# Motor_Driver_Board_V1_0.net
KiCad netlist of a schematic drawn in Altium Designer
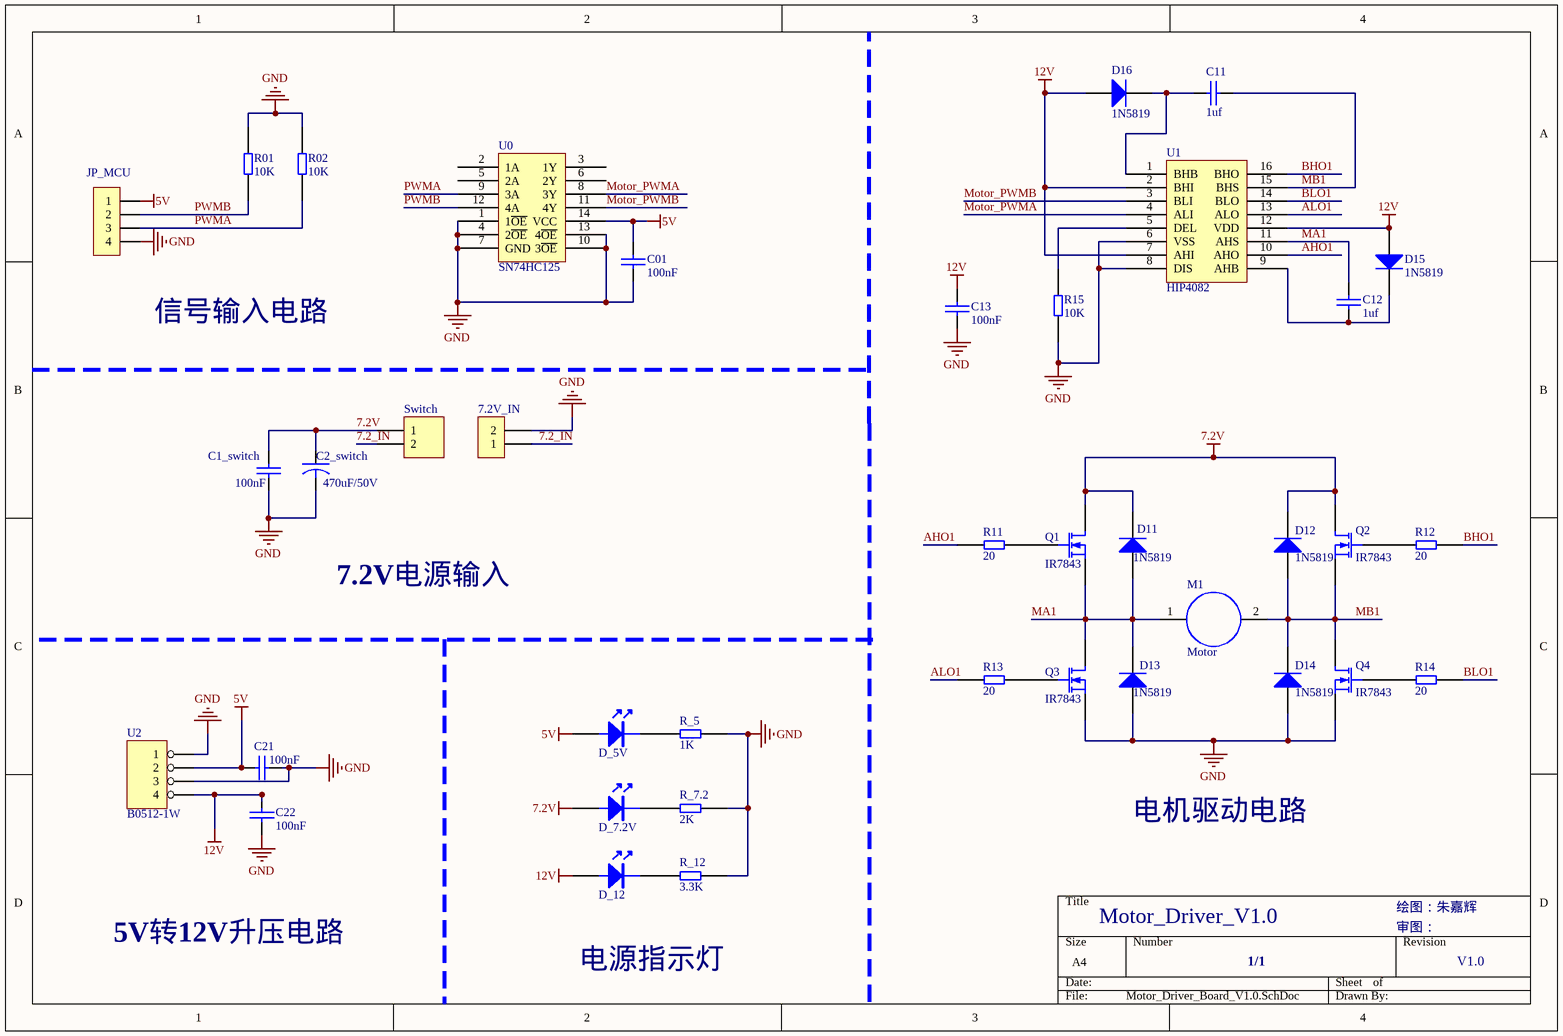
[diagram p0: Motor_Driver_Board_V1.0.SchDoc]

(export (version "E")
  (design (tool "Eeschema 10.0.6"))
  (components
    (comp (ref "7.2V_IN")
      (value "CON2")
      (footprint "KF301-2P")
      (description "Connector")
      (libsource (lib "Protel99Lib_SCH") (part "CON2"))
    )
    (comp (ref "C01")
      (value "100nF")
      (footprint "0805C")
      (description "Capacitor")
      (libsource (lib "Protel99Lib_SCH") (part "CAP"))
    )
    (comp (ref "C1_switch")
      (value "100nF")
      (footprint "0805C")
      (description "Capacitor")
      (libsource (lib "Protel99Lib_SCH") (part "CAP"))
    )
    (comp (ref "C2_switch")
      (value "470uF/50V")
      (footprint "RB.2/.4")
      (description "Capacitor")
      (libsource (lib "Protel99Lib_SCH") (part "CAPACITOR"))
    )
    (comp (ref "C11")
      (value "1uf")
      (footprint "0805C")
      (description "Capacitor")
      (libsource (lib "Protel99Lib_SCH") (part "CAP"))
    )
    (comp (ref "C12")
      (value "1uf")
      (footprint "0805C")
      (description "Capacitor")
      (libsource (lib "Protel99Lib_SCH") (part "CAP"))
    )
    (comp (ref "C13")
      (value "100nF")
      (footprint "0805C")
      (description "Capacitor")
      (libsource (lib "Protel99Lib_SCH") (part "CAP"))
    )
    (comp (ref "C21")
      (value "100nF")
      (footprint "0805C")
      (description "Capacitor")
      (libsource (lib "Protel99Lib_SCH") (part "CAP"))
    )
    (comp (ref "C22")
      (value "100nF")
      (footprint "0805C")
      (description "Capacitor")
      (libsource (lib "Protel99Lib_SCH") (part "CAP"))
    )
    (comp (ref "D11")
      (value "1N5819")
      (footprint "1N5819")
      (description "Default Diode")
      (fields (field (name "PUBLISHER") "Altium Limited"))
      (libsource (lib "Miscellaneous Devices") (part "Diode"))
    )
    (comp (ref "D12")
      (value "1N5819")
      (footprint "1N5819")
      (description "Default Diode")
      (fields (field (name "PUBLISHER") "Altium Limited"))
      (libsource (lib "Miscellaneous Devices") (part "Diode"))
    )
    (comp (ref "D13")
      (value "1N5819")
      (footprint "1N5819")
      (description "Default Diode")
      (fields (field (name "PUBLISHER") "Altium Limited"))
      (libsource (lib "Miscellaneous Devices") (part "Diode"))
    )
    (comp (ref "D14")
      (value "1N5819")
      (footprint "1N5819")
      (description "Default Diode")
      (fields (field (name "PUBLISHER") "Altium Limited"))
      (libsource (lib "Miscellaneous Devices") (part "Diode"))
    )
    (comp (ref "D15")
      (value "1N5819")
      (footprint "1N5819")
      (description "Default Diode")
      (fields (field (name "PUBLISHER") "Altium Limited"))
      (libsource (lib "Miscellaneous Devices") (part "Diode"))
    )
    (comp (ref "D16")
      (value "1N5819")
      (footprint "1N5819")
      (description "Default Diode")
      (fields (field (name "PUBLISHER") "Altium Limited"))
      (libsource (lib "Miscellaneous Devices") (part "Diode"))
    )
    (comp (ref "D_5V") (value "LED") (footprint "1206LED") (libsource (lib "Protel99Lib_SCH") (part "LED")))
    (comp (ref "D_7.2V") (value "LED") (footprint "1206LED") (libsource (lib "Protel99Lib_SCH") (part "LED")))
    (comp (ref "D_12") (value "LED") (footprint "1206LED") (libsource (lib "Protel99Lib_SCH") (part "LED")))
    (comp (ref "JP_MCU")
      (value "HDR-1X4")
      (footprint "XH2.54-WI-4P")
      (description "4P接插件")
      (fields (field (name "版权归属") "封装库来自淘宝 ID：黄晶宝石"))
      (libsource (lib "5.3 - 接插件-脚距2.54 (100mil) ") (part "Header 4"))
    )
    (comp (ref "M1")
      (value "Motor")
      (footprint "KF301-2P")
      (libsource (lib "Protel99Lib_SCH") (part "METER"))
    )
    (comp (ref "Q1")
      (value "IR7843")
      (footprint "LR7843")
      (description "N-Channel MOSFET")
      (fields (field (name "PUBLISHER") "Altium Limited"))
      (libsource (lib "Miscellaneous Devices") (part "MOSFET-N"))
    )
    (comp (ref "Q2")
      (value "IR7843")
      (footprint "LR7843")
      (description "N-Channel MOSFET")
      (fields (field (name "PUBLISHER") "Altium Limited"))
      (libsource (lib "Miscellaneous Devices") (part "MOSFET-N"))
    )
    (comp (ref "Q3")
      (value "IR7843")
      (footprint "LR7843")
      (description "N-Channel MOSFET")
      (fields (field (name "PUBLISHER") "Altium Limited"))
      (libsource (lib "Miscellaneous Devices") (part "MOSFET-N"))
    )
    (comp (ref "Q4")
      (value "IR7843")
      (footprint "LR7843")
      (description "N-Channel MOSFET")
      (fields (field (name "PUBLISHER") "Altium Limited"))
      (libsource (lib "Miscellaneous Devices") (part "MOSFET-N"))
    )
    (comp (ref "R01") (value "10K") (footprint "0805") (libsource (lib "BaseLib_SCH") (part "RES")))
    (comp (ref "R02") (value "10K") (footprint "0805") (libsource (lib "BaseLib_SCH") (part "RES")))
    (comp (ref "R11") (value "20") (footprint "0805") (libsource (lib "BaseLib_SCH") (part "RES")))
    (comp (ref "R12") (value "20") (footprint "0805") (libsource (lib "BaseLib_SCH") (part "RES")))
    (comp (ref "R13") (value "20") (footprint "0805") (libsource (lib "BaseLib_SCH") (part "RES")))
    (comp (ref "R14") (value "20") (footprint "0805") (libsource (lib "BaseLib_SCH") (part "RES")))
    (comp (ref "R15") (value "10K") (footprint "0805") (libsource (lib "BaseLib_SCH") (part "RES")))
    (comp (ref "R_5") (value "1K") (footprint "0805") (libsource (lib "BaseLib_SCH") (part "RES")))
    (comp (ref "R_7.2") (value "2K") (footprint "0805") (libsource (lib "BaseLib_SCH") (part "RES")))
    (comp (ref "R_12") (value "3.3K") (footprint "0805") (libsource (lib "BaseLib_SCH") (part "RES")))
    (comp (ref "Switch")
      (value "Header 2")
      (footprint "SWITCH-MINI")
      (description "Header, 2-Pin")
      (fields (field (name "PUBLISHER") "Altium Limited"))
      (libsource (lib "Miscellaneous Connectors") (part "Header 2"))
    )
    (comp (ref "U0")
      (value "SN74HC125")
      (footprint "SOP14_N")
      (libsource (lib "电机驱动原理图库") (part "SN74LVC125"))
    )
    (comp (ref "U1") (value "HIP4082") (footprint "SOP16_N") (libsource (lib "Schlib1") (part "HIP4082")))
    (comp (ref "U2")
      (value "B0512-1W")
      (footprint "SIP4_B_S-1W")
      (description "4 Pin Header")
      (libsource (lib "Protel99Lib_SCH") (part "4 HEADER"))
    )
  )
  (nets
    (net (code "1") (name "/7.2_IN") (class "Default")
      (node (ref "7.2V_IN") (pin "1") (pinfunction "1_1") (pintype "passive"))
      (node (ref "Switch") (pin "2") (pinfunction "2_2") (pintype "passive"))
    )
    (net (code "2") (name "/AHO1") (class "Default")
      (node (ref "R11") (pin "1") (pinfunction "1_1") (pintype "passive"))
      (node (ref "U1") (pin "10") (pinfunction "AHO_10") (pintype "passive"))
    )
    (net (code "3") (name "/ALO1") (class "Default")
      (node (ref "R13") (pin "1") (pinfunction "1_1") (pintype "passive"))
      (node (ref "U1") (pin "13") (pinfunction "ALO_13") (pintype "passive"))
    )
    (net (code "4") (name "/BHO1") (class "Default")
      (node (ref "R12") (pin "2") (pinfunction "2_2") (pintype "passive"))
      (node (ref "U1") (pin "16") (pinfunction "BHO_16") (pintype "passive"))
    )
    (net (code "5") (name "/BLO1") (class "Default")
      (node (ref "R14") (pin "2") (pinfunction "2_2") (pintype "passive"))
      (node (ref "U1") (pin "14") (pinfunction "BLO_14") (pintype "passive"))
    )
    (net (code "6") (name "/MA1") (class "Default")
      (node (ref "C12") (pin "2") (pinfunction "2_2") (pintype "passive"))
      (node (ref "D11") (pin "1") (pinfunction "A_1") (pintype "passive"))
      (node (ref "D13") (pin "2") (pinfunction "K_2") (pintype "passive"))
      (node (ref "M1") (pin "1") (pinfunction "1_1") (pintype "passive"))
      (node (ref "Q1") (pin "3") (pinfunction "S_3") (pintype "passive"))
      (node (ref "Q3") (pin "1") (pinfunction "D_1") (pintype "passive"))
      (node (ref "U1") (pin "11") (pinfunction "AHS_11") (pintype "passive"))
    )
    (net (code "7") (name "/MB1") (class "Default")
      (node (ref "C11") (pin "2") (pinfunction "2_2") (pintype "passive"))
      (node (ref "D12") (pin "1") (pinfunction "A_1") (pintype "passive"))
      (node (ref "D14") (pin "2") (pinfunction "K_2") (pintype "passive"))
      (node (ref "M1") (pin "2") (pinfunction "2_2") (pintype "passive"))
      (node (ref "Q2") (pin "3") (pinfunction "S_3") (pintype "passive"))
      (node (ref "Q4") (pin "1") (pinfunction "D_1") (pintype "passive"))
      (node (ref "U1") (pin "15") (pinfunction "BHS_15") (pintype "passive"))
    )
    (net (code "8") (name "/Motor_PWMA") (class "Default")
      (node (ref "U0") (pin "8") (pinfunction "3Y_8") (pintype "passive"))
      (node (ref "U1") (pin "4") (pinfunction "ALI_4") (pintype "passive"))
    )
    (net (code "9") (name "/Motor_PWMB") (class "Default")
      (node (ref "U0") (pin "11") (pinfunction "4Y_11") (pintype "passive"))
      (node (ref "U1") (pin "3") (pinfunction "BLI_3") (pintype "passive"))
    )
    (net (code "10") (name "/PWMA") (class "Default")
      (node (ref "JP_MCU") (pin "3") (pinfunction "3_3") (pintype "passive"))
      (node (ref "R02") (pin "1") (pinfunction "1_1") (pintype "passive"))
      (node (ref "U0") (pin "9") (pinfunction "3A_9") (pintype "passive"))
    )
    (net (code "11") (name "/PWMB") (class "Default")
      (node (ref "JP_MCU") (pin "2") (pinfunction "2_2") (pintype "passive"))
      (node (ref "R01") (pin "1") (pinfunction "1_1") (pintype "passive"))
      (node (ref "U0") (pin "12") (pinfunction "4A_12") (pintype "passive"))
    )
    (net (code "12") (name "5V") (class "Default")
      (node (ref "C01") (pin "2") (pinfunction "2_2") (pintype "passive"))
      (node (ref "C21") (pin "1") (pinfunction "1_1") (pintype "passive"))
      (node (ref "D_5V") (pin "A") (pinfunction "1_A") (pintype "passive"))
      (node (ref "JP_MCU") (pin "1") (pinfunction "1_1") (pintype "passive"))
      (node (ref "U0") (pin "14") (pinfunction "VCC_14") (pintype "passive"))
      (node (ref "U2") (pin "2") (pinfunction "2_2") (pintype "passive"))
    )
    (net (code "13") (name "7.2V") (class "Default")
      (node (ref "C1_switch") (pin "1") (pinfunction "1_1") (pintype "passive"))
      (node (ref "C2_switch") (pin "1") (pinfunction "1_1") (pintype "passive"))
      (node (ref "D11") (pin "2") (pinfunction "K_2") (pintype "passive"))
      (node (ref "D12") (pin "2") (pinfunction "K_2") (pintype "passive"))
      (node (ref "D_7.2V") (pin "A") (pinfunction "1_A") (pintype "passive"))
      (node (ref "Q1") (pin "1") (pinfunction "D_1") (pintype "passive"))
      (node (ref "Q2") (pin "1") (pinfunction "D_1") (pintype "passive"))
      (node (ref "Switch") (pin "1") (pinfunction "1_1") (pintype "passive"))
    )
    (net (code "14") (name "12V") (class "Default")
      (node (ref "C13") (pin "1") (pinfunction "1_1") (pintype "passive"))
      (node (ref "C22") (pin "2") (pinfunction "2_2") (pintype "passive"))
      (node (ref "D15") (pin "1") (pinfunction "A_1") (pintype "passive"))
      (node (ref "D16") (pin "1") (pinfunction "A_1") (pintype "passive"))
      (node (ref "D_12") (pin "A") (pinfunction "1_A") (pintype "passive"))
      (node (ref "U1") (pin "12") (pinfunction "VDD_12") (pintype "passive"))
      (node (ref "U1") (pin "2") (pinfunction "BHI_2") (pintype "passive"))
      (node (ref "U1") (pin "7") (pinfunction "AHI_7") (pintype "passive"))
      (node (ref "U2") (pin "4") (pinfunction "4_4") (pintype "passive"))
    )
    (net (code "15") (name "GND") (class "Default")
      (node (ref "7.2V_IN") (pin "2") (pinfunction "2_2") (pintype "passive"))
      (node (ref "C01") (pin "1") (pinfunction "1_1") (pintype "passive"))
      (node (ref "C13") (pin "2") (pinfunction "2_2") (pintype "passive"))
      (node (ref "C1_switch") (pin "2") (pinfunction "2_2") (pintype "passive"))
      (node (ref "C21") (pin "2") (pinfunction "2_2") (pintype "passive"))
      (node (ref "C22") (pin "1") (pinfunction "1_1") (pintype "passive"))
      (node (ref "C2_switch") (pin "2") (pinfunction "2_2") (pintype "passive"))
      (node (ref "D13") (pin "1") (pinfunction "A_1") (pintype "passive"))
      (node (ref "D14") (pin "1") (pinfunction "A_1") (pintype "passive"))
      (node (ref "JP_MCU") (pin "4") (pinfunction "4_4") (pintype "passive"))
      (node (ref "Q3") (pin "3") (pinfunction "S_3") (pintype "passive"))
      (node (ref "Q4") (pin "3") (pinfunction "S_3") (pintype "passive"))
      (node (ref "R01") (pin "2") (pinfunction "2_2") (pintype "passive"))
      (node (ref "R02") (pin "2") (pinfunction "2_2") (pintype "passive"))
      (node (ref "R15") (pin "1") (pinfunction "1_1") (pintype "passive"))
      (node (ref "R_12") (pin "1") (pinfunction "1_1") (pintype "passive"))
      (node (ref "R_5") (pin "1") (pinfunction "1_1") (pintype "passive"))
      (node (ref "R_7.2") (pin "1") (pinfunction "1_1") (pintype "passive"))
      (node (ref "U0") (pin "1") (pinfunction "1~{OE}_1") (pintype "passive"))
      (node (ref "U0") (pin "10") (pinfunction "3~{OE}_10") (pintype "passive"))
      (node (ref "U0") (pin "13") (pinfunction "4~{OE}_13") (pintype "passive"))
      (node (ref "U0") (pin "4") (pinfunction "2~{OE}_4") (pintype "passive"))
      (node (ref "U0") (pin "7") (pinfunction "GND_7") (pintype "passive"))
      (node (ref "U1") (pin "6") (pinfunction "VSS_6") (pintype "passive"))
      (node (ref "U1") (pin "8") (pinfunction "DIS_8") (pintype "passive"))
      (node (ref "U2") (pin "1") (pinfunction "1_1") (pintype "passive"))
      (node (ref "U2") (pin "3") (pinfunction "3_3") (pintype "passive"))
    )
    (net (code "16") (name "Net-(D15-K)") (class "Default")
      (node (ref "C12") (pin "1") (pinfunction "1_1") (pintype "passive"))
      (node (ref "D15") (pin "2") (pinfunction "K_2") (pintype "passive"))
      (node (ref "U1") (pin "9") (pinfunction "AHB_9") (pintype "passive"))
    )
    (net (code "17") (name "Net-(D16-K)") (class "Default")
      (node (ref "C11") (pin "1") (pinfunction "1_1") (pintype "passive"))
      (node (ref "D16") (pin "2") (pinfunction "K_2") (pintype "passive"))
      (node (ref "U1") (pin "1") (pinfunction "BHB_1") (pintype "passive"))
    )
    (net (code "18") (name "Net-(Q1-G)") (class "Default")
      (node (ref "Q1") (pin "2") (pinfunction "G_2") (pintype "passive"))
      (node (ref "R11") (pin "2") (pinfunction "2_2") (pintype "passive"))
    )
    (net (code "19") (name "Net-(Q2-G)") (class "Default")
      (node (ref "Q2") (pin "2") (pinfunction "G_2") (pintype "passive"))
      (node (ref "R12") (pin "1") (pinfunction "1_1") (pintype "passive"))
    )
    (net (code "20") (name "Net-(Q3-G)") (class "Default")
      (node (ref "Q3") (pin "2") (pinfunction "G_2") (pintype "passive"))
      (node (ref "R13") (pin "2") (pinfunction "2_2") (pintype "passive"))
    )
    (net (code "21") (name "Net-(Q4-G)") (class "Default")
      (node (ref "Q4") (pin "2") (pinfunction "G_2") (pintype "passive"))
      (node (ref "R14") (pin "1") (pinfunction "1_1") (pintype "passive"))
    )
    (net (code "22") (name "Net-(U1-DEL)") (class "Default")
      (node (ref "R15") (pin "2") (pinfunction "2_2") (pintype "passive"))
      (node (ref "U1") (pin "5") (pinfunction "DEL_5") (pintype "passive"))
    )
    (net (code "23") (name "unconnected-(D_5V-2-PadK)") (class "Default")
      (node (ref "D_5V") (pin "K") (pinfunction "2_K") (pintype "passive"))
    )
    (net (code "24") (name "unconnected-(D_7.2V-2-PadK)") (class "Default")
      (node (ref "D_7.2V") (pin "K") (pinfunction "2_K") (pintype "passive"))
    )
    (net (code "25") (name "unconnected-(D_12-2-PadK)") (class "Default")
      (node (ref "D_12") (pin "K") (pinfunction "2_K") (pintype "passive"))
    )
    (net (code "26") (name "unconnected-(R_5-Pad2)") (class "Default")
      (node (ref "R_5") (pin "2") (pinfunction "2_2") (pintype "passive"))
    )
    (net (code "27") (name "unconnected-(R_7.2-Pad2)") (class "Default")
      (node (ref "R_7.2") (pin "2") (pinfunction "2_2") (pintype "passive"))
    )
    (net (code "28") (name "unconnected-(R_12-Pad2)") (class "Default")
      (node (ref "R_12") (pin "2") (pinfunction "2_2") (pintype "passive"))
    )
    (net (code "29") (name "unconnected-(U0-1A-Pad2)") (class "Default")
      (node (ref "U0") (pin "2") (pinfunction "1A_2") (pintype "passive"))
    )
    (net (code "30") (name "unconnected-(U0-1Y-Pad3)") (class "Default")
      (node (ref "U0") (pin "3") (pinfunction "1Y_3") (pintype "passive"))
    )
    (net (code "31") (name "unconnected-(U0-2A-Pad5)") (class "Default")
      (node (ref "U0") (pin "5") (pinfunction "2A_5") (pintype "passive"))
    )
    (net (code "32") (name "unconnected-(U0-2Y-Pad6)") (class "Default")
      (node (ref "U0") (pin "6") (pinfunction "2Y_6") (pintype "passive"))
    )
  )
)
